# StepDown.net
KiCad netlist of a schematic drawn in EAGLE
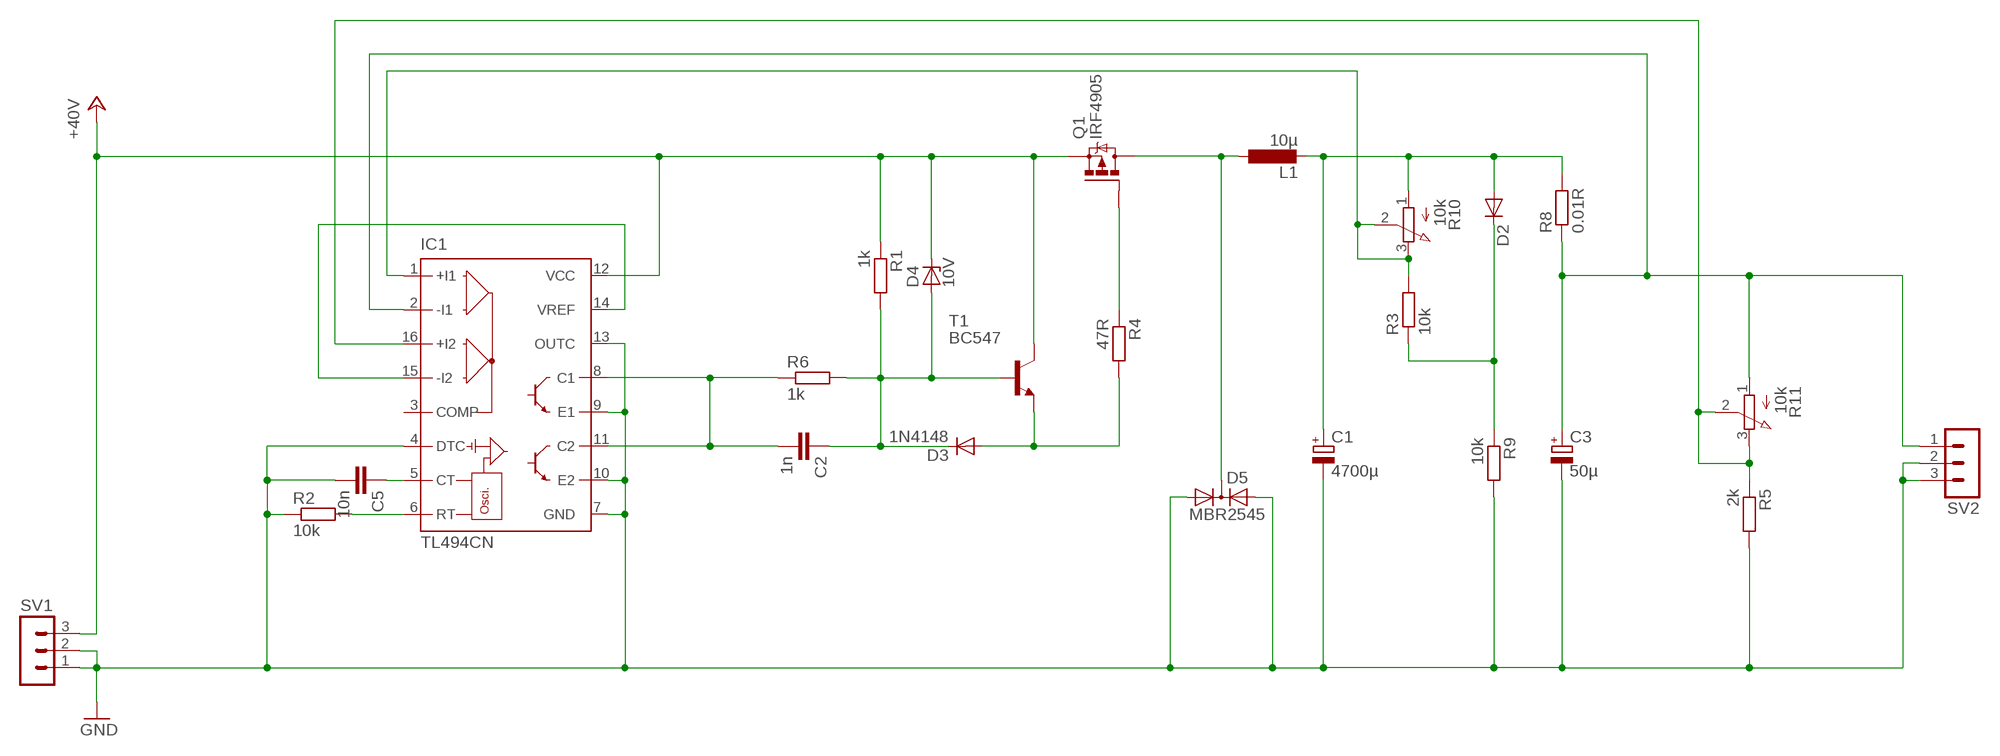
[diagram p0: schematic, sheet 1]

(export (version "E")
  (design (tool "Eeschema 10.0.6"))
  (components
    (comp (ref "C1")
      (value "4700µ")
      (footprint "eagle-import:EB20D")
      (libsource (lib "eagle-import") (part "CPOL-EUE10-20"))
    )
    (comp (ref "C2")
      (value "1n")
      (footprint "eagle-import:C025-040X050")
      (libsource (lib "eagle-import") (part "C-EU025-040X050"))
    )
    (comp (ref "C3")
      (value "50µ")
      (footprint "eagle-import:E2,5-7")
      (libsource (lib "eagle-import") (part "CPOL-EUE2.5-7"))
    )
    (comp (ref "C5")
      (value "10n")
      (footprint "eagle-import:C075-032X103")
      (libsource (lib "eagle-import") (part "C-EU075-032X103"))
    )
    (comp (ref "D2")
      (value "DIODE-D-10")
      (footprint "eagle-import:D-10")
      (libsource (lib "eagle-import") (part "DIODE-D-10"))
    )
    (comp (ref "D3")
      (value "1N4148")
      (footprint "eagle-import:D-2.5")
      (libsource (lib "eagle-import") (part "DIODE-D-2.5"))
    )
    (comp (ref "D4")
      (value "10V")
      (footprint "eagle-import:ZDIO-2.5")
      (libsource (lib "eagle-import") (part "ZENER-DIODEZD-2.5"))
    )
    (comp (ref "D5")
      (value "MBR2545")
      (footprint "eagle-import:TO3P")
      (libsource (lib "eagle-import") (part "DIODE-2AC|CATO3P"))
    )
    (comp (ref "IC1")
      (value "TL494CN")
      (footprint "eagle-import:DIL16")
      (libsource (lib "eagle-import") (part "TL494NC"))
    )
    (comp (ref "L1")
      (value "10µ")
      (footprint "eagle-import:TFI0307")
      (libsource (lib "eagle-import") (part "L-EUTFI0307"))
    )
    (comp (ref "Q1")
      (value "IRF4905")
      (footprint "eagle-import:TO220BH")
      (libsource (lib "eagle-import") (part "IRF4905"))
    )
    (comp (ref "R1")
      (value "1k")
      (footprint "eagle-import:0204V")
      (libsource (lib "eagle-import") (part "R-EU_0204/2V"))
    )
    (comp (ref "R2")
      (value "10k")
      (footprint "eagle-import:0204V")
      (libsource (lib "eagle-import") (part "R-EU_0204/2V"))
    )
    (comp (ref "R3")
      (value "10k")
      (footprint "eagle-import:0204V")
      (libsource (lib "eagle-import") (part "R-EU_0204/2V"))
    )
    (comp (ref "R4")
      (value "47R")
      (footprint "eagle-import:0204V")
      (libsource (lib "eagle-import") (part "R-EU_0204/2V"))
    )
    (comp (ref "R5")
      (value "2k")
      (footprint "eagle-import:0207_12")
      (libsource (lib "eagle-import") (part "R-EU_0207/12"))
    )
    (comp (ref "R6")
      (value "1k")
      (footprint "eagle-import:0204V")
      (libsource (lib "eagle-import") (part "R-EU_0204/2V"))
    )
    (comp (ref "R8")
      (value "0.01R")
      (footprint "eagle-import:0617V")
      (libsource (lib "eagle-import") (part "R-EU_0617/5V"))
    )
    (comp (ref "R9")
      (value "10k")
      (footprint "eagle-import:0204V")
      (libsource (lib "eagle-import") (part "R-EU_0204/2V"))
    )
    (comp (ref "R10")
      (value "10k")
      (footprint "eagle-import:EVUE")
      (libsource (lib "eagle-import") (part "EVUE2A"))
    )
    (comp (ref "R11")
      (value "10k")
      (footprint "eagle-import:EVUE")
      (libsource (lib "eagle-import") (part "EVUE2A"))
    )
    (comp (ref "SV1")
      (value "MA03-1")
      (footprint "eagle-import:MA03-1")
      (libsource (lib "eagle-import") (part "MA03-1"))
    )
    (comp (ref "SV2")
      (value "MA03-1")
      (footprint "eagle-import:MA03-1")
      (libsource (lib "eagle-import") (part "MA03-1"))
    )
    (comp (ref "T1")
      (value "BC547")
      (footprint "eagle-import:TO92-CBE")
      (libsource (lib "eagle-import") (part "-NPN-TO92-CBEBC547"))
    )
  )
  (nets
    (net (code "1") (name "+40V") (class "Default")
      (node (ref "D4") (pin "C") (pinfunction "C_C") (pintype "passive"))
      (node (ref "IC1") (pin "12") (pinfunction "VCC_12") (pintype "power_in"))
      (node (ref "Q1") (pin "S") (pinfunction "S_S") (pintype "passive"))
      (node (ref "R1") (pin "1") (pinfunction "1_1") (pintype "passive"))
      (node (ref "SV1") (pin "3") (pinfunction "3_3") (pintype "passive"))
      (node (ref "T1") (pin "C") (pinfunction "C_C") (pintype "passive"))
    )
    (net (code "2") (name "GND") (class "Default")
      (node (ref "C1") (pin "-") (pinfunction "-_-") (pintype "passive"))
      (node (ref "C3") (pin "-") (pinfunction "-_-") (pintype "passive"))
      (node (ref "C5") (pin "2") (pinfunction "2_2") (pintype "passive"))
      (node (ref "D5") (pin "1") (pinfunction "A1_1") (pintype "passive"))
      (node (ref "D5") (pin "3") (pinfunction "A2_3") (pintype "passive"))
      (node (ref "IC1") (pin "10") (pinfunction "E2_10") (pintype "passive"))
      (node (ref "IC1") (pin "13") (pinfunction "OUTC_13") (pintype "output"))
      (node (ref "IC1") (pin "4") (pinfunction "DTC_4") (pintype "input"))
      (node (ref "IC1") (pin "7") (pinfunction "GND_7") (pintype "power_in"))
      (node (ref "IC1") (pin "9") (pinfunction "E1_9") (pintype "passive"))
      (node (ref "R2") (pin "1") (pinfunction "1_1") (pintype "passive"))
      (node (ref "R5") (pin "2") (pinfunction "2_2") (pintype "passive"))
      (node (ref "R9") (pin "2") (pinfunction "2_2") (pintype "passive"))
      (node (ref "SV1") (pin "1") (pinfunction "1_1") (pintype "passive"))
      (node (ref "SV1") (pin "2") (pinfunction "2_2") (pintype "passive"))
      (node (ref "SV2") (pin "2") (pinfunction "2_2") (pintype "passive"))
      (node (ref "SV2") (pin "3") (pinfunction "3_3") (pintype "passive"))
    )
    (net (code "3") (name "Net-(C2-Pad1)") (class "Default")
      (node (ref "C2") (pin "1") (pinfunction "1_1") (pintype "passive"))
      (node (ref "D3") (pin "C") (pinfunction "C_C") (pintype "passive"))
      (node (ref "D4") (pin "A") (pinfunction "A_A") (pintype "passive"))
      (node (ref "R1") (pin "2") (pinfunction "2_2") (pintype "passive"))
      (node (ref "R6") (pin "2") (pinfunction "2_2") (pintype "passive"))
      (node (ref "T1") (pin "B") (pinfunction "B_B") (pintype "passive"))
    )
    (net (code "4") (name "Net-(D2-PadC)") (class "Default")
      (node (ref "D2") (pin "C") (pinfunction "C_C") (pintype "passive"))
      (node (ref "R3") (pin "1") (pinfunction "1_1") (pintype "passive"))
      (node (ref "R9") (pin "1") (pinfunction "1_1") (pintype "passive"))
    )
    (net (code "5") (name "Net-(D3-PadA)") (class "Default")
      (node (ref "D3") (pin "A") (pinfunction "A_A") (pintype "passive"))
      (node (ref "R4") (pin "2") (pinfunction "2_2") (pintype "passive"))
      (node (ref "T1") (pin "E") (pinfunction "E_E") (pintype "passive"))
    )
    (net (code "6") (name "Net-(D5-C)") (class "Default")
      (node (ref "D5") (pin "2") (pinfunction "C_2") (pintype "passive"))
      (node (ref "L1") (pin "1") (pinfunction "1_1") (pintype "passive"))
      (node (ref "Q1") (pin "D") (pinfunction "D_D") (pintype "passive"))
    )
    (net (code "7") (name "Net-(IC1-+I1)") (class "Default")
      (node (ref "IC1") (pin "1") (pinfunction "+I1_1") (pintype "input"))
      (node (ref "R10") (pin "2") (pinfunction "S_2") (pintype "passive"))
      (node (ref "R10") (pin "3") (pinfunction "E_3") (pintype "passive"))
      (node (ref "R3") (pin "2") (pinfunction "2_2") (pintype "passive"))
    )
    (net (code "8") (name "Net-(IC1-+I2)") (class "Default")
      (node (ref "IC1") (pin "16") (pinfunction "+I2_16") (pintype "input"))
      (node (ref "R11") (pin "2") (pinfunction "S_2") (pintype "passive"))
      (node (ref "R11") (pin "3") (pinfunction "E_3") (pintype "passive"))
      (node (ref "R5") (pin "1") (pinfunction "1_1") (pintype "passive"))
    )
    (net (code "9") (name "Net-(IC1--I1)") (class "Default")
      (node (ref "C3") (pin "+") (pinfunction "+_+") (pintype "passive"))
      (node (ref "IC1") (pin "2") (pinfunction "-I1_2") (pintype "input"))
      (node (ref "R11") (pin "1") (pinfunction "A_1") (pintype "passive"))
      (node (ref "R8") (pin "1") (pinfunction "1_1") (pintype "passive"))
      (node (ref "SV2") (pin "1") (pinfunction "1_1") (pintype "passive"))
    )
    (net (code "10") (name "Net-(IC1--I2)") (class "Default")
      (node (ref "IC1") (pin "14") (pinfunction "VREF_14") (pintype "input"))
      (node (ref "IC1") (pin "15") (pinfunction "-I2_15") (pintype "input"))
    )
    (net (code "11") (name "Net-(IC1-C1)") (class "Default")
      (node (ref "C2") (pin "2") (pinfunction "2_2") (pintype "passive"))
      (node (ref "IC1") (pin "11") (pinfunction "C2_11") (pintype "passive"))
      (node (ref "IC1") (pin "8") (pinfunction "C1_8") (pintype "passive"))
      (node (ref "R6") (pin "1") (pinfunction "1_1") (pintype "passive"))
    )
    (net (code "12") (name "Net-(IC1-CT)") (class "Default")
      (node (ref "C5") (pin "1") (pinfunction "1_1") (pintype "passive"))
      (node (ref "IC1") (pin "5") (pinfunction "CT_5") (pintype "input"))
    )
    (net (code "13") (name "Net-(IC1-RT)") (class "Default")
      (node (ref "IC1") (pin "6") (pinfunction "RT_6") (pintype "input"))
      (node (ref "R2") (pin "2") (pinfunction "2_2") (pintype "passive"))
    )
    (net (code "14") (name "Net-(Q1-PadG)") (class "Default")
      (node (ref "Q1") (pin "G") (pinfunction "G_G") (pintype "passive"))
      (node (ref "R4") (pin "1") (pinfunction "1_1") (pintype "passive"))
    )
    (net (code "15") (name "Net-(R10-A)") (class "Default")
      (node (ref "C1") (pin "+") (pinfunction "+_+") (pintype "passive"))
      (node (ref "D2") (pin "A") (pinfunction "A_A") (pintype "passive"))
      (node (ref "L1") (pin "2") (pinfunction "2_2") (pintype "passive"))
      (node (ref "R10") (pin "1") (pinfunction "A_1") (pintype "passive"))
      (node (ref "R8") (pin "2") (pinfunction "2_2") (pintype "passive"))
    )
    (net (code "16") (name "unconnected-(IC1-COMP-Pad3)") (class "Default")
      (node (ref "IC1") (pin "3") (pinfunction "COMP_3") (pintype "passive"))
    )
  )
)
